# Rov3_zasilanie.net
KiCad netlist of a schematic drawn in EAGLE
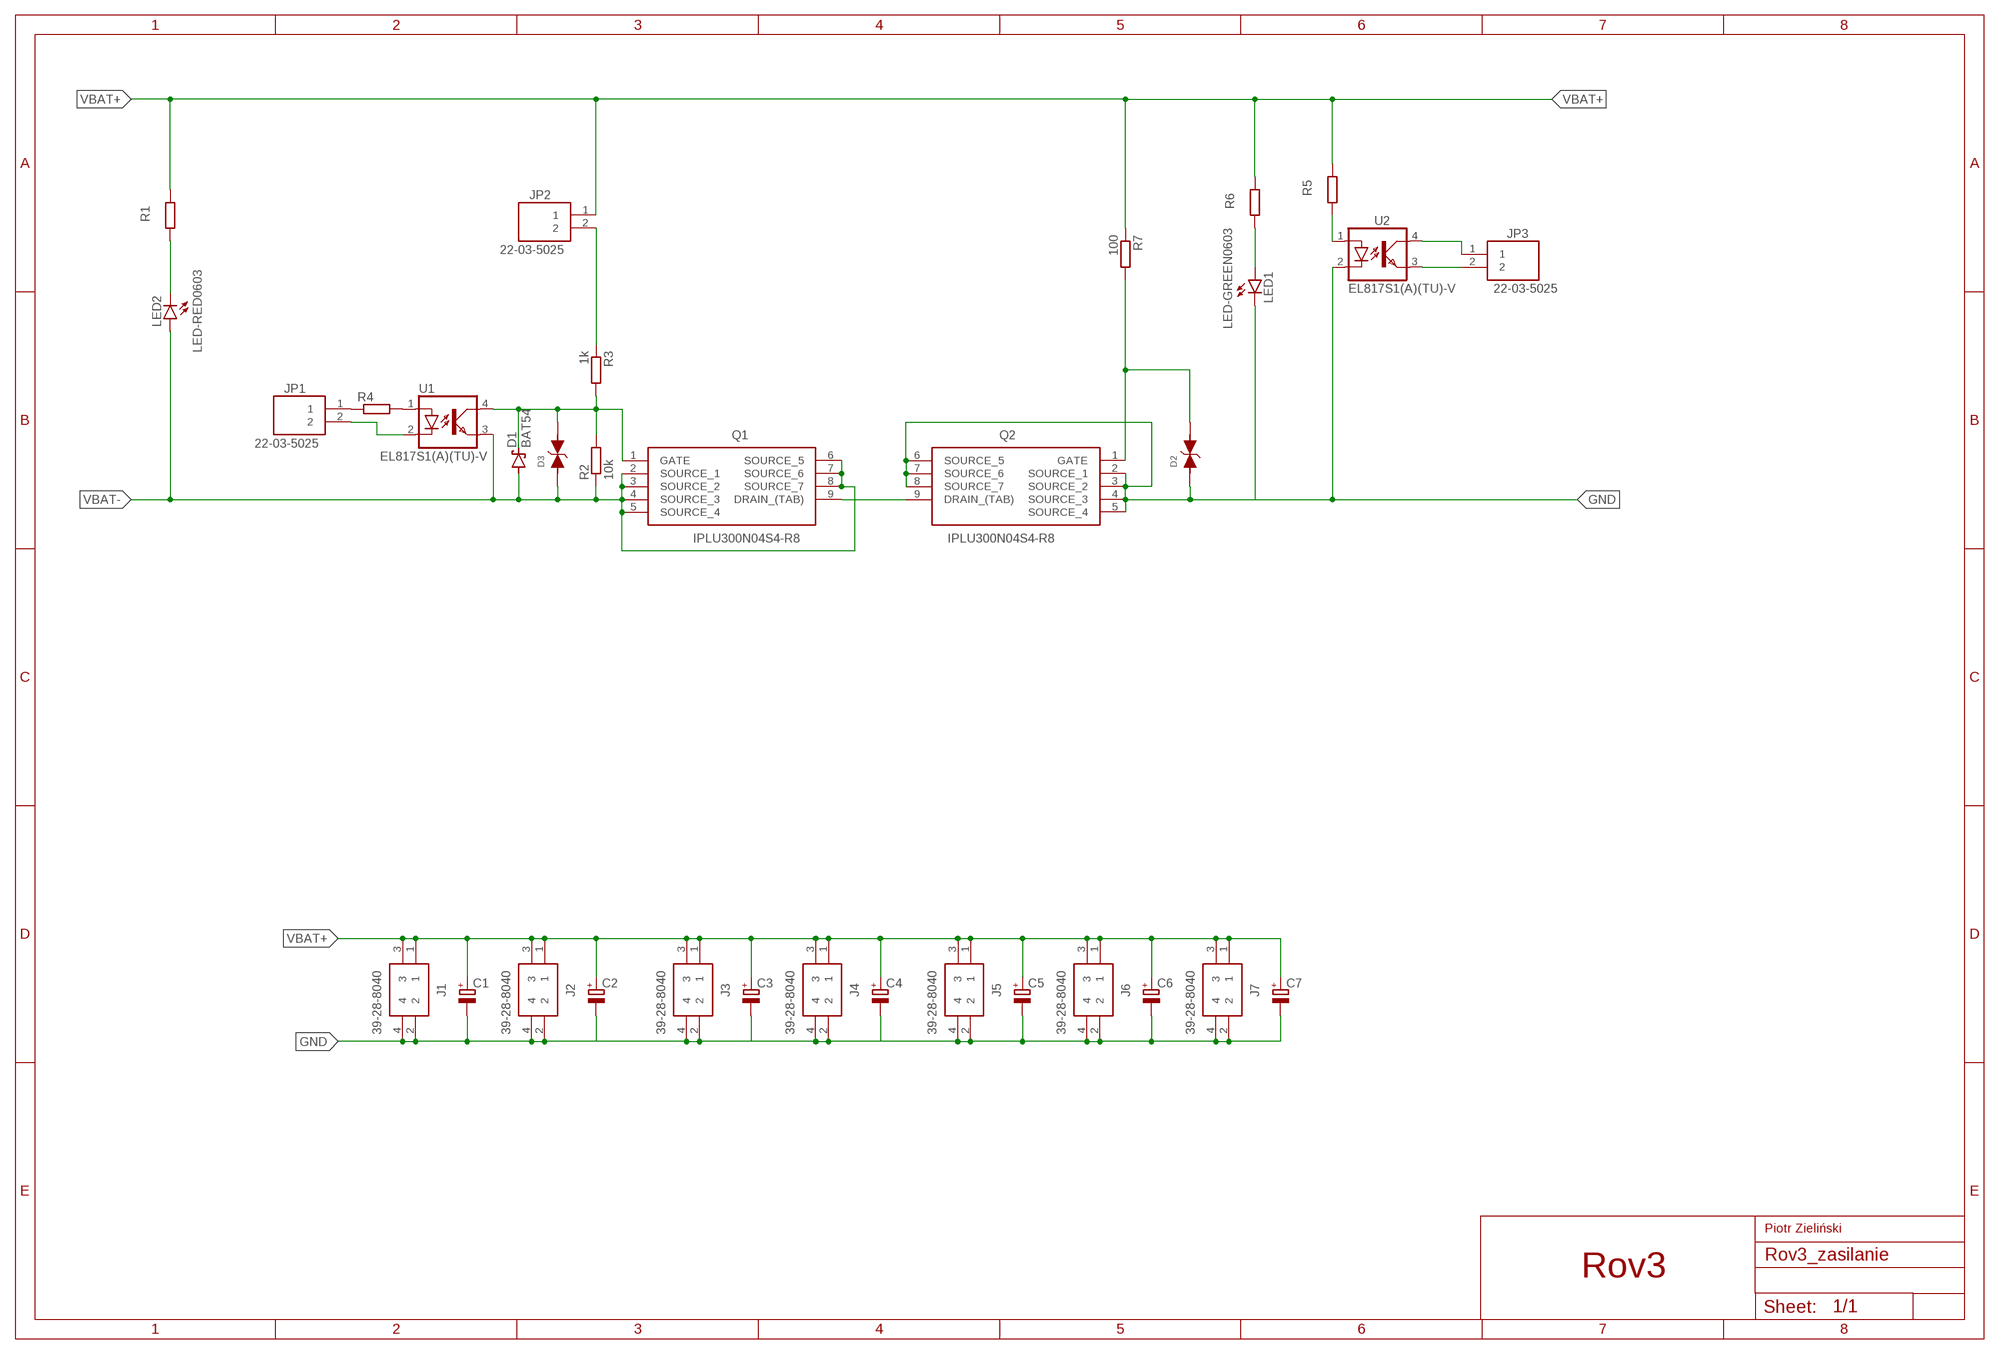
[diagram p0: schematic, sheet 1]

(export (version "E")
  (design (tool "Eeschema 10.0.6"))
  (components
    (comp (ref "C1")
      (value "CPOL-EUE5-10.5")
      (footprint "eagle-import:E5-10,5")
      (libsource (lib "eagle-import") (part "CPOL-EUE5-10.5"))
    )
    (comp (ref "C2")
      (value "CPOL-EUE5-10.5")
      (footprint "eagle-import:E5-10,5")
      (libsource (lib "eagle-import") (part "CPOL-EUE5-10.5"))
    )
    (comp (ref "C3")
      (value "CPOL-EUE5-10.5")
      (footprint "eagle-import:E5-10,5")
      (libsource (lib "eagle-import") (part "CPOL-EUE5-10.5"))
    )
    (comp (ref "C4")
      (value "CPOL-EUE5-10.5")
      (footprint "eagle-import:E5-10,5")
      (libsource (lib "eagle-import") (part "CPOL-EUE5-10.5"))
    )
    (comp (ref "C5")
      (value "CPOL-EUE5-10.5")
      (footprint "eagle-import:E5-10,5")
      (libsource (lib "eagle-import") (part "CPOL-EUE5-10.5"))
    )
    (comp (ref "C6")
      (value "CPOL-EUE5-10.5")
      (footprint "eagle-import:E5-10,5")
      (libsource (lib "eagle-import") (part "CPOL-EUE5-10.5"))
    )
    (comp (ref "C7")
      (value "CPOL-EUE5-10.5")
      (footprint "eagle-import:E5-10,5")
      (libsource (lib "eagle-import") (part "CPOL-EUE5-10.5"))
    )
    (comp (ref "D1")
      (value "BAT54")
      (footprint "eagle-import:SOT23")
      (libsource (lib "eagle-import") (part "BAT54"))
    )
    (comp (ref "D2")
      (value "WE-TVSP_BI_400W_824501221")
      (footprint "eagle-import:VARTVSP_SMA_DO-214AC")
      (libsource (lib "eagle-import") (part "WE-TVSP_BI_400W_824501221"))
    )
    (comp (ref "D3")
      (value "WE-TVSP_BI_400W_824501221")
      (footprint "eagle-import:VARTVSP_SMA_DO-214AC")
      (libsource (lib "eagle-import") (part "WE-TVSP_BI_400W_824501221"))
    )
    (comp (ref "J1")
      (value "39-28-8040")
      (footprint "eagle-import:MOLEX_2X2_PCB_SOCKET")
      (fields (field (name "MOUSER_PART_NUMBER") "538-39-28-8040"))
      (libsource (lib "eagle-import") (part "39-28-8040"))
    )
    (comp (ref "J2")
      (value "39-28-8040")
      (footprint "eagle-import:MOLEX_2X2_PCB_SOCKET")
      (fields (field (name "MOUSER_PART_NUMBER") "538-39-28-8040"))
      (libsource (lib "eagle-import") (part "39-28-8040"))
    )
    (comp (ref "J3")
      (value "39-28-8040")
      (footprint "eagle-import:MOLEX_2X2_PCB_SOCKET")
      (fields (field (name "MOUSER_PART_NUMBER") "538-39-28-8040"))
      (libsource (lib "eagle-import") (part "39-28-8040"))
    )
    (comp (ref "J4")
      (value "39-28-8040")
      (footprint "eagle-import:MOLEX_2X2_PCB_SOCKET")
      (fields (field (name "MOUSER_PART_NUMBER") "538-39-28-8040"))
      (libsource (lib "eagle-import") (part "39-28-8040"))
    )
    (comp (ref "J5")
      (value "39-28-8040")
      (footprint "eagle-import:MOLEX_2X2_PCB_SOCKET")
      (fields (field (name "MOUSER_PART_NUMBER") "538-39-28-8040"))
      (libsource (lib "eagle-import") (part "39-28-8040"))
    )
    (comp (ref "J6")
      (value "39-28-8040")
      (footprint "eagle-import:MOLEX_2X2_PCB_SOCKET")
      (fields (field (name "MOUSER_PART_NUMBER") "538-39-28-8040"))
      (libsource (lib "eagle-import") (part "39-28-8040"))
    )
    (comp (ref "J7")
      (value "39-28-8040")
      (footprint "eagle-import:MOLEX_2X2_PCB_SOCKET")
      (fields (field (name "MOUSER_PART_NUMBER") "538-39-28-8040"))
      (libsource (lib "eagle-import") (part "39-28-8040"))
    )
    (comp (ref "JP1")
      (value "22-03-5025")
      (footprint "eagle-import:2.50MM_MINI-SPOX_2PIN_PCB_SOCKET")
      (fields (field (name "MOUSER_PART_NUMBER") "538-22-03-5025"))
      (libsource (lib "eagle-import") (part "22-03-5025"))
    )
    (comp (ref "JP2")
      (value "22-03-5025")
      (footprint "eagle-import:2.50MM_MINI-SPOX_2PIN_PCB_SOCKET")
      (fields (field (name "MOUSER_PART_NUMBER") "538-22-03-5025"))
      (libsource (lib "eagle-import") (part "22-03-5025"))
    )
    (comp (ref "JP3")
      (value "22-03-5025")
      (footprint "eagle-import:2.50MM_MINI-SPOX_2PIN_PCB_SOCKET")
      (fields (field (name "MOUSER_PART_NUMBER") "538-22-03-5025"))
      (libsource (lib "eagle-import") (part "22-03-5025"))
    )
    (comp (ref "LED1")
      (value "LED-GREEN0603")
      (footprint "eagle-import:0603-GREEN")
      (libsource (lib "eagle-import") (part "LED-GREEN0603"))
    )
    (comp (ref "LED2")
      (value "LED-RED0603")
      (footprint "eagle-import:0603-RED")
      (libsource (lib "eagle-import") (part "LED-RED0603"))
    )
    (comp (ref "Q1")
      (value "IPLU300N04S4-R8")
      (footprint "eagle-import:PG-HSOF-8-1")
      (fields (field (name "MOUSER_PART_NUMBER") "726-IPLU300N04S4-R8"))
      (libsource (lib "eagle-import") (part "IPLU300N04S4-R8"))
    )
    (comp (ref "Q2")
      (value "IPLU300N04S4-R8")
      (footprint "eagle-import:PG-HSOF-8-1")
      (fields (field (name "MOUSER_PART_NUMBER") "726-IPLU300N04S4-R8"))
      (libsource (lib "eagle-import") (part "IPLU300N04S4-R8"))
    )
    (comp (ref "R1")
      (value "R-EU_R0805")
      (footprint "eagle-import:R0805")
      (libsource (lib "eagle-import") (part "R-EU_R0805"))
    )
    (comp (ref "R2")
      (value "10k")
      (footprint "eagle-import:R0805")
      (libsource (lib "eagle-import") (part "R-EU_R0805"))
    )
    (comp (ref "R3")
      (value "1k")
      (footprint "eagle-import:R0805")
      (libsource (lib "eagle-import") (part "R-EU_R0805"))
    )
    (comp (ref "R4")
      (value "R-EU_R0805")
      (footprint "eagle-import:R0805")
      (libsource (lib "eagle-import") (part "R-EU_R0805"))
    )
    (comp (ref "R5")
      (value "R-EU_R0805")
      (footprint "eagle-import:R0805")
      (libsource (lib "eagle-import") (part "R-EU_R0805"))
    )
    (comp (ref "R6")
      (value "R-EU_R0805")
      (footprint "eagle-import:R0805")
      (libsource (lib "eagle-import") (part "R-EU_R0805"))
    )
    (comp (ref "R7")
      (value "100")
      (footprint "eagle-import:R0805")
      (libsource (lib "eagle-import") (part "R-EU_R0805"))
    )
    (comp (ref "U1")
      (value "EL817S1(A)(TU)-V")
      (footprint "eagle-import:SOIC254P1030X390-4N_EL817S1(A)(TU)-V")
      (fields (field (name "MF") "Everlight Electronics") (field (name "MP") "EL817S1_A__TU_-V"))
      (libsource (lib "eagle-import") (part "EL817S1(A)(TU)-V"))
    )
    (comp (ref "U2")
      (value "EL817S1(A)(TU)-V")
      (footprint "eagle-import:SOIC254P1030X390-4N_EL817S1(A)(TU)-V")
      (fields (field (name "MF") "Everlight Electronics") (field (name "MP") "EL817S1_A__TU_-V"))
      (libsource (lib "eagle-import") (part "EL817S1(A)(TU)-V"))
    )
  )
  (nets
    (net (code "1") (name "GND") (class "Default")
      (node (ref "C1") (pin "-") (pinfunction "-_-") (pintype "passive"))
      (node (ref "C2") (pin "-") (pinfunction "-_-") (pintype "passive"))
      (node (ref "C3") (pin "-") (pinfunction "-_-") (pintype "passive"))
      (node (ref "C4") (pin "-") (pinfunction "-_-") (pintype "passive"))
      (node (ref "C5") (pin "-") (pinfunction "-_-") (pintype "passive"))
      (node (ref "C6") (pin "-") (pinfunction "-_-") (pintype "passive"))
      (node (ref "C7") (pin "-") (pinfunction "-_-") (pintype "passive"))
      (node (ref "D2") (pin "1") (pinfunction "1_1") (pintype "passive"))
      (node (ref "J1") (pin "2") (pinfunction "2_2") (pintype "bidirectional"))
      (node (ref "J1") (pin "4") (pinfunction "4_4") (pintype "bidirectional"))
      (node (ref "J2") (pin "2") (pinfunction "2_2") (pintype "bidirectional"))
      (node (ref "J2") (pin "4") (pinfunction "4_4") (pintype "bidirectional"))
      (node (ref "J3") (pin "2") (pinfunction "2_2") (pintype "bidirectional"))
      (node (ref "J3") (pin "4") (pinfunction "4_4") (pintype "bidirectional"))
      (node (ref "J4") (pin "2") (pinfunction "2_2") (pintype "bidirectional"))
      (node (ref "J4") (pin "4") (pinfunction "4_4") (pintype "bidirectional"))
      (node (ref "J5") (pin "2") (pinfunction "2_2") (pintype "bidirectional"))
      (node (ref "J5") (pin "4") (pinfunction "4_4") (pintype "bidirectional"))
      (node (ref "J6") (pin "2") (pinfunction "2_2") (pintype "bidirectional"))
      (node (ref "J6") (pin "4") (pinfunction "4_4") (pintype "bidirectional"))
      (node (ref "J7") (pin "2") (pinfunction "2_2") (pintype "bidirectional"))
      (node (ref "J7") (pin "4") (pinfunction "4_4") (pintype "bidirectional"))
      (node (ref "LED1") (pin "C") (pinfunction "C_C") (pintype "passive"))
      (node (ref "Q2") (pin "2") (pinfunction "SOURCE_1_2") (pintype "bidirectional"))
      (node (ref "Q2") (pin "3") (pinfunction "SOURCE_2_3") (pintype "bidirectional"))
      (node (ref "Q2") (pin "4") (pinfunction "SOURCE_3_4") (pintype "bidirectional"))
      (node (ref "Q2") (pin "5") (pinfunction "SOURCE_4_5") (pintype "bidirectional"))
      (node (ref "Q2") (pin "6") (pinfunction "SOURCE_5_6") (pintype "bidirectional"))
      (node (ref "Q2") (pin "7") (pinfunction "SOURCE_6_7") (pintype "bidirectional"))
      (node (ref "Q2") (pin "8") (pinfunction "SOURCE_7_8") (pintype "bidirectional"))
      (node (ref "U2") (pin "2") (pinfunction "C_2") (pintype "passive"))
    )
    (net (code "2") (name "Net-(D1-C)") (class "Default")
      (node (ref "D1") (pin "3") (pinfunction "C_3") (pintype "passive"))
      (node (ref "D3") (pin "2") (pinfunction "2_2") (pintype "passive"))
      (node (ref "Q1") (pin "1") (pinfunction "GATE_1") (pintype "bidirectional"))
      (node (ref "R2") (pin "2") (pinfunction "2_2") (pintype "passive"))
      (node (ref "R3") (pin "2") (pinfunction "2_2") (pintype "passive"))
      (node (ref "U1") (pin "4") (pinfunction "COL_4") (pintype "passive"))
    )
    (net (code "3") (name "Net-(JP1-Pad1)") (class "Default")
      (node (ref "JP1") (pin "1") (pinfunction "1_1") (pintype "bidirectional"))
      (node (ref "R4") (pin "1") (pinfunction "1_1") (pintype "passive"))
    )
    (net (code "4") (name "Net-(JP2-Pad2)") (class "Default")
      (node (ref "JP2") (pin "2") (pinfunction "2_2") (pintype "bidirectional"))
      (node (ref "R3") (pin "1") (pinfunction "1_1") (pintype "passive"))
    )
    (net (code "5") (name "Net-(LED1-PadA)") (class "Default")
      (node (ref "LED1") (pin "A") (pinfunction "A_A") (pintype "passive"))
      (node (ref "R6") (pin "1") (pinfunction "1_1") (pintype "passive"))
    )
    (net (code "6") (name "Net-(LED2-PadC)") (class "Default")
      (node (ref "LED2") (pin "C") (pinfunction "C_C") (pintype "passive"))
      (node (ref "R1") (pin "1") (pinfunction "1_1") (pintype "passive"))
    )
    (net (code "7") (name "Net-(Q1-DRAIN_(TAB))") (class "Default")
      (node (ref "Q1") (pin "9") (pinfunction "DRAIN_(TAB)_9") (pintype "bidirectional"))
      (node (ref "Q2") (pin "9") (pinfunction "DRAIN_(TAB)_9") (pintype "bidirectional"))
    )
    (net (code "8") (name "Net-(Q2-GATE)") (class "Default")
      (node (ref "D2") (pin "2") (pinfunction "2_2") (pintype "passive"))
      (node (ref "Q2") (pin "1") (pinfunction "GATE_1") (pintype "bidirectional"))
      (node (ref "R7") (pin "2") (pinfunction "2_2") (pintype "passive"))
    )
    (net (code "9") (name "Net-(U1-A)") (class "Default")
      (node (ref "R4") (pin "2") (pinfunction "2_2") (pintype "passive"))
      (node (ref "U1") (pin "1") (pinfunction "A_1") (pintype "passive"))
    )
    (net (code "10") (name "Net-(U1-C)") (class "Default")
      (node (ref "JP1") (pin "2") (pinfunction "2_2") (pintype "bidirectional"))
      (node (ref "U1") (pin "2") (pinfunction "C_2") (pintype "passive"))
    )
    (net (code "11") (name "Net-(U2-A)") (class "Default")
      (node (ref "R5") (pin "1") (pinfunction "1_1") (pintype "passive"))
      (node (ref "U2") (pin "1") (pinfunction "A_1") (pintype "passive"))
    )
    (net (code "12") (name "Net-(U2-COL)") (class "Default")
      (node (ref "JP3") (pin "1") (pinfunction "1_1") (pintype "bidirectional"))
      (node (ref "U2") (pin "4") (pinfunction "COL_4") (pintype "passive"))
    )
    (net (code "13") (name "Net-(U2-EMIT)") (class "Default")
      (node (ref "JP3") (pin "2") (pinfunction "2_2") (pintype "bidirectional"))
      (node (ref "U2") (pin "3") (pinfunction "EMIT_3") (pintype "passive"))
    )
    (net (code "14") (name "VBAT+") (class "Default")
      (node (ref "C1") (pin "+") (pinfunction "+_+") (pintype "passive"))
      (node (ref "C2") (pin "+") (pinfunction "+_+") (pintype "passive"))
      (node (ref "C3") (pin "+") (pinfunction "+_+") (pintype "passive"))
      (node (ref "C4") (pin "+") (pinfunction "+_+") (pintype "passive"))
      (node (ref "C5") (pin "+") (pinfunction "+_+") (pintype "passive"))
      (node (ref "C6") (pin "+") (pinfunction "+_+") (pintype "passive"))
      (node (ref "C7") (pin "+") (pinfunction "+_+") (pintype "passive"))
      (node (ref "J1") (pin "1") (pinfunction "1_1") (pintype "bidirectional"))
      (node (ref "J1") (pin "3") (pinfunction "3_3") (pintype "bidirectional"))
      (node (ref "J2") (pin "1") (pinfunction "1_1") (pintype "bidirectional"))
      (node (ref "J2") (pin "3") (pinfunction "3_3") (pintype "bidirectional"))
      (node (ref "J3") (pin "1") (pinfunction "1_1") (pintype "bidirectional"))
      (node (ref "J3") (pin "3") (pinfunction "3_3") (pintype "bidirectional"))
      (node (ref "J4") (pin "1") (pinfunction "1_1") (pintype "bidirectional"))
      (node (ref "J4") (pin "3") (pinfunction "3_3") (pintype "bidirectional"))
      (node (ref "J5") (pin "1") (pinfunction "1_1") (pintype "bidirectional"))
      (node (ref "J5") (pin "3") (pinfunction "3_3") (pintype "bidirectional"))
      (node (ref "J6") (pin "1") (pinfunction "1_1") (pintype "bidirectional"))
      (node (ref "J6") (pin "3") (pinfunction "3_3") (pintype "bidirectional"))
      (node (ref "J7") (pin "1") (pinfunction "1_1") (pintype "bidirectional"))
      (node (ref "J7") (pin "3") (pinfunction "3_3") (pintype "bidirectional"))
      (node (ref "JP2") (pin "1") (pinfunction "1_1") (pintype "bidirectional"))
      (node (ref "R1") (pin "2") (pinfunction "2_2") (pintype "passive"))
      (node (ref "R5") (pin "2") (pinfunction "2_2") (pintype "passive"))
      (node (ref "R6") (pin "2") (pinfunction "2_2") (pintype "passive"))
      (node (ref "R7") (pin "1") (pinfunction "1_1") (pintype "passive"))
    )
    (net (code "15") (name "VBAT-") (class "Default")
      (node (ref "D1") (pin "1") (pinfunction "A_1") (pintype "passive"))
      (node (ref "D3") (pin "1") (pinfunction "1_1") (pintype "passive"))
      (node (ref "LED2") (pin "A") (pinfunction "A_A") (pintype "passive"))
      (node (ref "Q1") (pin "2") (pinfunction "SOURCE_1_2") (pintype "bidirectional"))
      (node (ref "Q1") (pin "3") (pinfunction "SOURCE_2_3") (pintype "bidirectional"))
      (node (ref "Q1") (pin "4") (pinfunction "SOURCE_3_4") (pintype "bidirectional"))
      (node (ref "Q1") (pin "5") (pinfunction "SOURCE_4_5") (pintype "bidirectional"))
      (node (ref "Q1") (pin "6") (pinfunction "SOURCE_5_6") (pintype "bidirectional"))
      (node (ref "Q1") (pin "7") (pinfunction "SOURCE_6_7") (pintype "bidirectional"))
      (node (ref "Q1") (pin "8") (pinfunction "SOURCE_7_8") (pintype "bidirectional"))
      (node (ref "R2") (pin "1") (pinfunction "1_1") (pintype "passive"))
      (node (ref "U1") (pin "3") (pinfunction "EMIT_3") (pintype "passive"))
    )
  )
)
